# design.net
KiCad netlist of a schematic drawn in Altium Designer
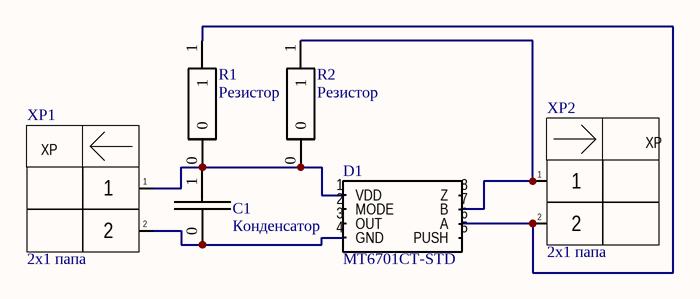
[diagram p0: Схема платы энкодера.SchDoc]

(export (version "E")
  (design (tool "Eeschema 10.0.6"))
  (components
    (comp (ref "C1")
      (value "Конденсатор")
      (footprint "0805 cap")
      (libsource (lib "gost_lib_UGO") (part "Конденсатор"))
    )
    (comp (ref "D1")
      (value "MT6701CT-STD")
      (footprint "SOP8")
      (description "Инкрементарный энкодер")
      (libsource (lib "gost_lib_UGO") (part "MT6701CT-STD"))
    )
    (comp (ref "R1")
      (value "Резистор")
      (footprint "0603 res")
      (libsource (lib "gost_lib_UGO") (part "Резистор"))
    )
    (comp (ref "R2")
      (value "Резистор")
      (footprint "0603 res")
      (libsource (lib "gost_lib_UGO") (part "Резистор"))
    )
    (comp (ref "XP1")
      (value "2x1 папа")
      (footprint "Питание разъём")
      (libsource (lib "gost_lib_UGO") (part "2x1 папа"))
    )
    (comp (ref "XP2")
      (value "2x1 папа")
      (footprint "Питание разъём")
      (libsource (lib "") (part "2x1 папа_1"))
    )
  )
  (nets
    (net (code "1") (name "Net-(D1-A)") (class "Default")
      (node (ref "D1") (pin "6") (pinfunction "A_6") (pintype "passive"))
      (node (ref "R1") (pin "1") (pinfunction "1_1") (pintype "passive"))
      (node (ref "XP2") (pin "2") (pinfunction "2_2") (pintype "passive"))
    )
    (net (code "2") (name "Net-(D1-B)") (class "Default")
      (node (ref "D1") (pin "7") (pinfunction "B_7") (pintype "passive"))
      (node (ref "R2") (pin "1") (pinfunction "1_1") (pintype "passive"))
      (node (ref "XP2") (pin "1") (pinfunction "1_1") (pintype "passive"))
    )
    (net (code "3") (name "Net-(D1-GND)") (class "Default")
      (node (ref "C1") (pin "0") (pintype "passive"))
      (node (ref "D1") (pin "4") (pinfunction "GND_4") (pintype "passive"))
      (node (ref "XP1") (pin "2") (pinfunction "2_2") (pintype "passive"))
    )
    (net (code "4") (name "Net-(D1-VDD)") (class "Default")
      (node (ref "C1") (pin "1") (pintype "passive"))
      (node (ref "D1") (pin "1") (pinfunction "VDD_1") (pintype "passive"))
      (node (ref "R1") (pin "0") (pinfunction "0_0") (pintype "passive"))
      (node (ref "R2") (pin "0") (pinfunction "0_0") (pintype "passive"))
      (node (ref "XP1") (pin "1") (pinfunction "1_1") (pintype "passive"))
    )
    (net (code "5") (name "unconnected-(D1-MODE-Pad2)") (class "Default")
      (node (ref "D1") (pin "2") (pinfunction "MODE_2") (pintype "passive"))
    )
    (net (code "6") (name "unconnected-(D1-OUT-Pad3)") (class "Default")
      (node (ref "D1") (pin "3") (pinfunction "OUT_3") (pintype "passive"))
    )
    (net (code "7") (name "unconnected-(D1-PUSH-Pad5)") (class "Default")
      (node (ref "D1") (pin "5") (pinfunction "PUSH_5") (pintype "passive"))
    )
    (net (code "8") (name "unconnected-(D1-Z-Pad8)") (class "Default")
      (node (ref "D1") (pin "8") (pinfunction "Z_8") (pintype "passive"))
    )
  )
)
